# driver2.net
KiCad netlist of a schematic drawn in Altium Designer
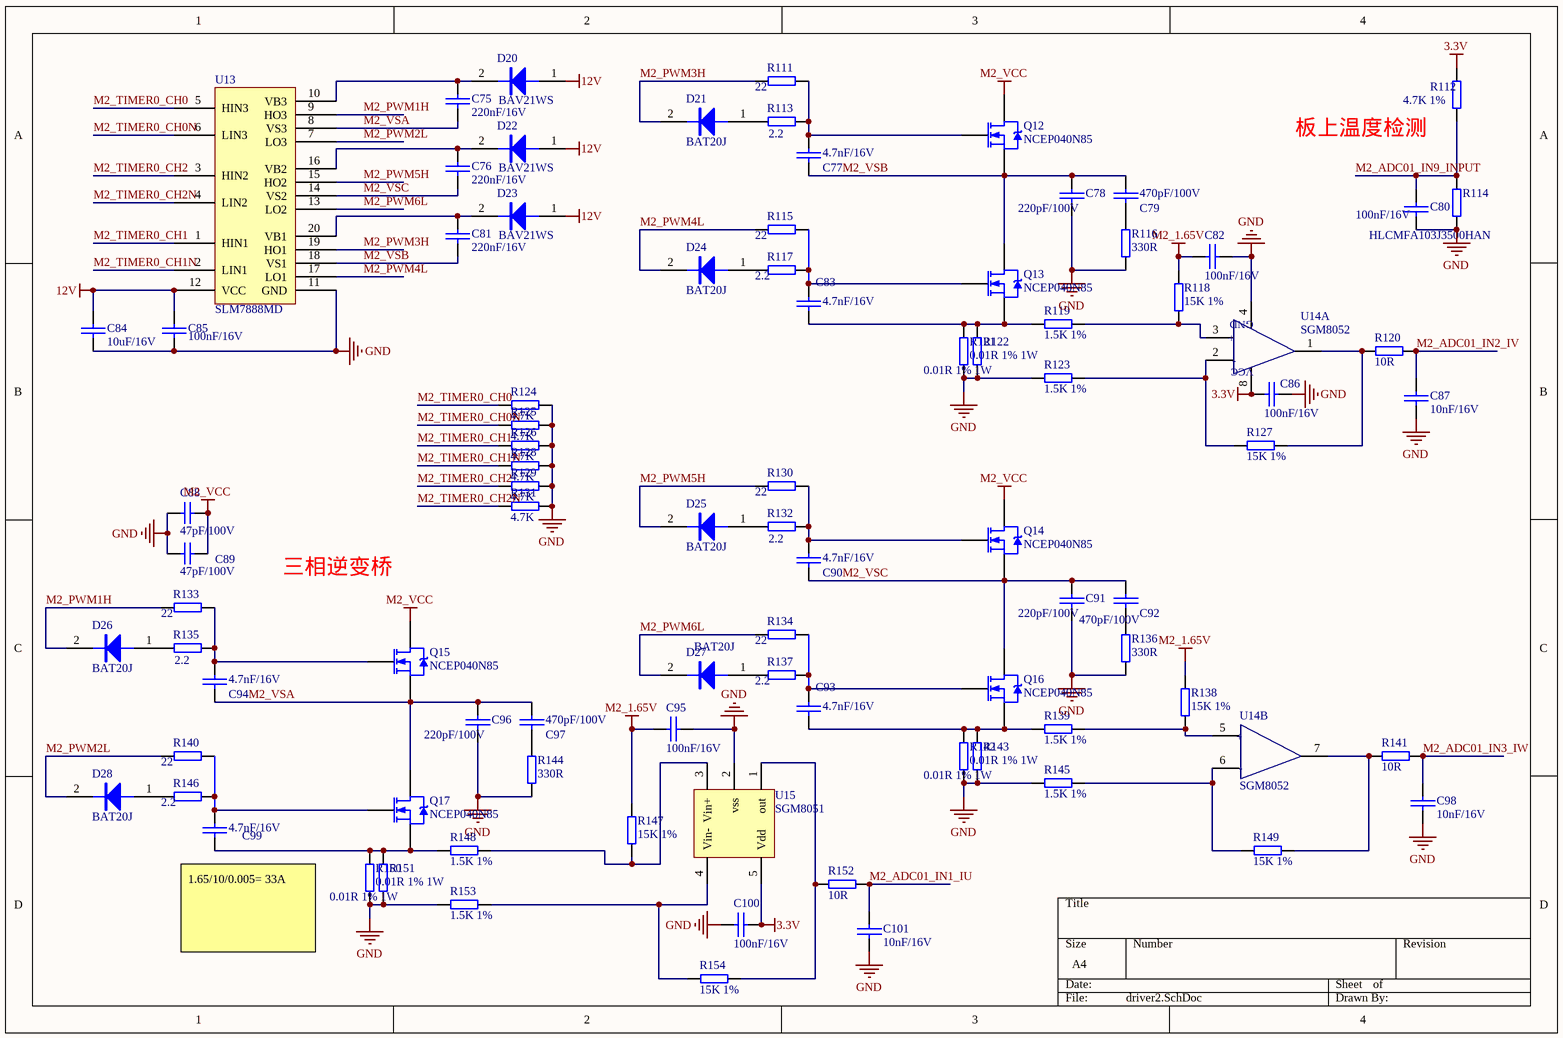
[diagram p0: driver2.SchDoc]

(export (version "E")
  (design (tool "Eeschema 10.0.6"))
  (components
    (comp (ref "C75")
      (value "220nF/16V")
      (footprint "C0402")
      (description "Capacitor")
      (libsource (lib "*") (part "CAP"))
    )
    (comp (ref "C76")
      (value "220nF/16V")
      (footprint "C0402")
      (description "Capacitor")
      (libsource (lib "*") (part "CAP"))
    )
    (comp (ref "C77")
      (value "4.7nF/16V")
      (footprint "C0402")
      (description "Capacitor")
      (libsource (lib "*") (part "CAP"))
    )
    (comp (ref "C78")
      (value "220pF/100V")
      (footprint "C0805")
      (description "Capacitor")
      (libsource (lib "*") (part "CAP"))
    )
    (comp (ref "C79")
      (value "470pF/100V")
      (footprint "C0805")
      (description "Capacitor")
      (libsource (lib "*") (part "CAP"))
    )
    (comp (ref "C80")
      (value "100nF/16V")
      (footprint "C0402")
      (description "Capacitor")
      (libsource (lib "*") (part "CAP"))
    )
    (comp (ref "C81")
      (value "220nF/16V")
      (footprint "C0402")
      (description "Capacitor")
      (libsource (lib "*") (part "CAP"))
    )
    (comp (ref "C82")
      (value "100nF/16V")
      (footprint "C0402")
      (description "Capacitor")
      (libsource (lib "*") (part "CAP"))
    )
    (comp (ref "C83")
      (value "4.7nF/16V")
      (footprint "C0402")
      (description "Capacitor")
      (libsource (lib "*") (part "CAP"))
    )
    (comp (ref "C84")
      (value "10uF/16V")
      (footprint "C0805")
      (description "Capacitor")
      (libsource (lib "*") (part "CAP"))
    )
    (comp (ref "C85")
      (value "100nF/16V")
      (footprint "C0603")
      (description "Capacitor")
      (libsource (lib "*") (part "CAP"))
    )
    (comp (ref "C86")
      (value "100nF/16V")
      (footprint "C0402")
      (description "Capacitor")
      (libsource (lib "*") (part "CAP"))
    )
    (comp (ref "C87")
      (value "10nF/16V")
      (footprint "C0402")
      (description "Capacitor")
      (libsource (lib "*") (part "CAP"))
    )
    (comp (ref "C88") (value "47pF/100V") (footprint "C1206") (libsource (lib "zijianku") (part "cap")))
    (comp (ref "C89") (value "47pF/100V") (footprint "C1206") (libsource (lib "zijianku") (part "cap")))
    (comp (ref "C90")
      (value "4.7nF/16V")
      (footprint "C0402")
      (description "Capacitor")
      (libsource (lib "*") (part "CAP"))
    )
    (comp (ref "C91")
      (value "220pF/100V")
      (footprint "C0805")
      (description "Capacitor")
      (libsource (lib "*") (part "CAP"))
    )
    (comp (ref "C92")
      (value "470pF/100V")
      (footprint "C0805")
      (description "Capacitor")
      (libsource (lib "*") (part "CAP"))
    )
    (comp (ref "C93")
      (value "4.7nF/16V")
      (footprint "C0402")
      (description "Capacitor")
      (libsource (lib "*") (part "CAP"))
    )
    (comp (ref "C94")
      (value "4.7nF/16V")
      (footprint "C0402")
      (description "Capacitor")
      (libsource (lib "*") (part "CAP"))
    )
    (comp (ref "C95")
      (value "100nF/16V")
      (footprint "C0402")
      (description "Capacitor")
      (libsource (lib "*") (part "CAP"))
    )
    (comp (ref "C96")
      (value "220pF/100V")
      (footprint "C0805")
      (description "Capacitor")
      (libsource (lib "*") (part "CAP"))
    )
    (comp (ref "C97")
      (value "470pF/100V")
      (footprint "C0805")
      (description "Capacitor")
      (libsource (lib "*") (part "CAP"))
    )
    (comp (ref "C98")
      (value "10nF/16V")
      (footprint "C0402")
      (description "Capacitor")
      (libsource (lib "*") (part "CAP"))
    )
    (comp (ref "C99")
      (value "4.7nF/16V")
      (footprint "C0402")
      (description "Capacitor")
      (libsource (lib "*") (part "CAP"))
    )
    (comp (ref "C100")
      (value "100nF/16V")
      (footprint "C0402")
      (description "Capacitor")
      (libsource (lib "*") (part "CAP"))
    )
    (comp (ref "C101")
      (value "10nF/16V")
      (footprint "C0402")
      (description "Capacitor")
      (libsource (lib "*") (part "CAP"))
    )
    (comp (ref "D20") (value "BAV21WS") (footprint "SOD-323") (libsource (lib "*") (part "DIODE")))
    (comp (ref "D21") (value "BAT20J") (footprint "SOD-323") (libsource (lib "*") (part "DIODE")))
    (comp (ref "D22") (value "BAV21WS") (footprint "SOD-323") (libsource (lib "*") (part "DIODE")))
    (comp (ref "D23") (value "BAV21WS") (footprint "SOD-323") (libsource (lib "*") (part "DIODE")))
    (comp (ref "D24") (value "BAT20J") (footprint "SOD-323") (libsource (lib "*") (part "DIODE")))
    (comp (ref "D25") (value "BAT20J") (footprint "SOD-323") (libsource (lib "*") (part "DIODE")))
    (comp (ref "D26") (value "BAT20J") (footprint "SOD-323") (libsource (lib "*") (part "DIODE")))
    (comp (ref "D27") (value "BAT20J") (footprint "SOD-323") (libsource (lib "*") (part "DIODE")))
    (comp (ref "D28") (value "BAT20J") (footprint "SOD-323") (libsource (lib "*") (part "DIODE")))
    (comp (ref "Q12")
      (value "NCEP040N85")
      (footprint "TO-220ABN")
      (libsource (lib "zijianku") (part "N-channel Enhancement MOS"))
    )
    (comp (ref "Q13")
      (value "NCEP040N85")
      (footprint "TO-220ABN")
      (libsource (lib "zijianku") (part "N-channel Enhancement MOS"))
    )
    (comp (ref "Q14")
      (value "NCEP040N85")
      (footprint "TO-220ABN")
      (libsource (lib "zijianku") (part "N-channel Enhancement MOS"))
    )
    (comp (ref "Q15")
      (value "NCEP040N85")
      (footprint "TO-220ABN")
      (libsource (lib "zijianku") (part "N-channel Enhancement MOS"))
    )
    (comp (ref "Q16")
      (value "NCEP040N85")
      (footprint "TO-220ABN")
      (libsource (lib "zijianku") (part "N-channel Enhancement MOS"))
    )
    (comp (ref "Q17")
      (value "NCEP040N85")
      (footprint "TO-220ABN")
      (libsource (lib "zijianku") (part "N-channel Enhancement MOS"))
    )
    (comp (ref "R111") (value "22") (footprint "R0603") (libsource (lib "*") (part "R")))
    (comp (ref "R112") (value "4.7K 1%") (footprint "R0402") (libsource (lib "*") (part "R")))
    (comp (ref "R113") (value "2.2") (footprint "R0603") (libsource (lib "*") (part "R")))
    (comp (ref "R114") (value "HLCMFA103J3500HAN") (footprint "R0603") (libsource (lib "*") (part "R")))
    (comp (ref "R115") (value "22") (footprint "R0603") (libsource (lib "*") (part "R")))
    (comp (ref "R116") (value "330R") (footprint "R1206") (libsource (lib "zijianku") (part "Resistance")))
    (comp (ref "R117") (value "2.2") (footprint "R0603") (libsource (lib "*") (part "R")))
    (comp (ref "R118") (value "15K 1%") (footprint "R0402") (libsource (lib "zijianku") (part "Resistance")))
    (comp (ref "R119") (value "1.5K 1%") (footprint "R0402") (libsource (lib "zijianku") (part "Resistance")))
    (comp (ref "R120") (value "10R") (footprint "R0402") (libsource (lib "zijianku") (part "Resistance")))
    (comp (ref "R121")
      (value "0.01R 1% 1W")
      (footprint "R1210")
      (libsource (lib "zijianku") (part "Resistance"))
    )
    (comp (ref "R122")
      (value "0.01R 1% 1W")
      (footprint "R1210")
      (libsource (lib "zijianku") (part "Resistance"))
    )
    (comp (ref "R123") (value "1.5K 1%") (footprint "R0402") (libsource (lib "zijianku") (part "Resistance")))
    (comp (ref "R124") (value "4.7K") (footprint "R0402") (libsource (lib "*") (part "R")))
    (comp (ref "R125") (value "4.7K") (footprint "R0402") (libsource (lib "*") (part "R")))
    (comp (ref "R126") (value "4.7K") (footprint "R0402") (libsource (lib "*") (part "R")))
    (comp (ref "R127") (value "15K 1%") (footprint "R0402") (libsource (lib "zijianku") (part "Resistance")))
    (comp (ref "R128") (value "4.7K") (footprint "R0402") (libsource (lib "*") (part "R")))
    (comp (ref "R129") (value "4.7K") (footprint "R0402") (libsource (lib "*") (part "R")))
    (comp (ref "R130") (value "22") (footprint "R0603") (libsource (lib "*") (part "R")))
    (comp (ref "R131") (value "4.7K") (footprint "R0402") (libsource (lib "*") (part "R")))
    (comp (ref "R132") (value "2.2") (footprint "R0603") (libsource (lib "*") (part "R")))
    (comp (ref "R133") (value "22") (footprint "R0603") (libsource (lib "*") (part "R")))
    (comp (ref "R134") (value "22") (footprint "R0603") (libsource (lib "*") (part "R")))
    (comp (ref "R135") (value "2.2") (footprint "R0603") (libsource (lib "*") (part "R")))
    (comp (ref "R136") (value "330R") (footprint "R1206") (libsource (lib "zijianku") (part "Resistance")))
    (comp (ref "R137") (value "2.2") (footprint "R0603") (libsource (lib "*") (part "R")))
    (comp (ref "R138") (value "15K 1%") (footprint "R0402") (libsource (lib "zijianku") (part "Resistance")))
    (comp (ref "R139") (value "1.5K 1%") (footprint "R0402") (libsource (lib "zijianku") (part "Resistance")))
    (comp (ref "R140") (value "22") (footprint "R0603") (libsource (lib "*") (part "R")))
    (comp (ref "R141") (value "10R") (footprint "R0402") (libsource (lib "zijianku") (part "Resistance")))
    (comp (ref "R142")
      (value "0.01R 1% 1W")
      (footprint "R1210")
      (libsource (lib "zijianku") (part "Resistance"))
    )
    (comp (ref "R143")
      (value "0.01R 1% 1W")
      (footprint "R1210")
      (libsource (lib "zijianku") (part "Resistance"))
    )
    (comp (ref "R144") (value "330R") (footprint "R1206") (libsource (lib "zijianku") (part "Resistance")))
    (comp (ref "R145") (value "1.5K 1%") (footprint "R0402") (libsource (lib "zijianku") (part "Resistance")))
    (comp (ref "R146") (value "2.2") (footprint "R0603") (libsource (lib "*") (part "R")))
    (comp (ref "R147") (value "15K 1%") (footprint "R0402") (libsource (lib "zijianku") (part "Resistance")))
    (comp (ref "R148") (value "1.5K 1%") (footprint "R0402") (libsource (lib "zijianku") (part "Resistance")))
    (comp (ref "R149") (value "15K 1%") (footprint "R0402") (libsource (lib "zijianku") (part "Resistance")))
    (comp (ref "R150")
      (value "0.01R 1% 1W")
      (footprint "R1210")
      (libsource (lib "zijianku") (part "Resistance"))
    )
    (comp (ref "R151")
      (value "0.01R 1% 1W")
      (footprint "R1210")
      (libsource (lib "zijianku") (part "Resistance"))
    )
    (comp (ref "R152") (value "10R") (footprint "R0402") (libsource (lib "zijianku") (part "Resistance")))
    (comp (ref "R153") (value "1.5K 1%") (footprint "R0402") (libsource (lib "zijianku") (part "Resistance")))
    (comp (ref "R154") (value "15K 1%") (footprint "R0402") (libsource (lib "zijianku") (part "Resistance")))
    (comp (ref "U13")
      (value "SLM7888MD")
      (footprint "TSSOP-20")
      (description "SILLUMIN")
      (libsource (lib "zijianku") (part "SLM7888"))
    )
    (comp (ref "U14")
      (value "SGM8052")
      (footprint "VSSOP/MSOP-8")
      (description "圣邦微电子")
      (libsource (lib "Common Device") (part "LM393"))
    )
    (comp (ref "U15")
      (value "SGM8051")
      (footprint "SOT-23(5)")
      (description "圣邦微电子")
      (libsource (lib "Common Device") (part "LMV7239"))
    )
  )
  (nets
    (net (code "1") (name "/M2_ADC01_IN1_IU") (class "Default")
      (node (ref "C101") (pin "1") (pinfunction "1_1") (pintype "passive"))
      (node (ref "R152") (pin "1") (pintype "passive"))
    )
    (net (code "2") (name "/M2_ADC01_IN2_IV") (class "Default")
      (node (ref "C87") (pin "1") (pinfunction "1_1") (pintype "passive"))
      (node (ref "R120") (pin "1") (pintype "passive"))
    )
    (net (code "3") (name "/M2_ADC01_IN3_IW") (class "Default")
      (node (ref "C98") (pin "1") (pinfunction "1_1") (pintype "passive"))
      (node (ref "R141") (pin "1") (pintype "passive"))
    )
    (net (code "4") (name "/M2_ADC01_IN9_INPUT") (class "Default")
      (node (ref "C80") (pin "1") (pinfunction "1_1") (pintype "passive"))
      (node (ref "R112") (pin "1") (pinfunction "1_1") (pintype "passive"))
      (node (ref "R114") (pin "2") (pinfunction "2_2") (pintype "passive"))
    )
    (net (code "5") (name "/M2_PWM1H") (class "Default")
      (node (ref "D26") (pin "2") (pinfunction "K_2") (pintype "passive"))
      (node (ref "R133") (pin "2") (pinfunction "2_2") (pintype "passive"))
      (node (ref "U13") (pin "9") (pinfunction "HO3_9") (pintype "passive"))
    )
    (net (code "6") (name "/M2_PWM2L") (class "Default")
      (node (ref "D28") (pin "2") (pinfunction "K_2") (pintype "passive"))
      (node (ref "R140") (pin "2") (pinfunction "2_2") (pintype "passive"))
      (node (ref "U13") (pin "7") (pinfunction "LO3_7") (pintype "passive"))
    )
    (net (code "7") (name "/M2_PWM3H") (class "Default")
      (node (ref "D21") (pin "2") (pinfunction "K_2") (pintype "passive"))
      (node (ref "R111") (pin "2") (pinfunction "2_2") (pintype "passive"))
      (node (ref "U13") (pin "19") (pinfunction "HO1_19") (pintype "passive"))
    )
    (net (code "8") (name "/M2_PWM4L") (class "Default")
      (node (ref "D24") (pin "2") (pinfunction "K_2") (pintype "passive"))
      (node (ref "R115") (pin "2") (pinfunction "2_2") (pintype "passive"))
      (node (ref "U13") (pin "17") (pinfunction "LO1_17") (pintype "passive"))
    )
    (net (code "9") (name "/M2_PWM5H") (class "Default")
      (node (ref "D25") (pin "2") (pinfunction "K_2") (pintype "passive"))
      (node (ref "R130") (pin "2") (pinfunction "2_2") (pintype "passive"))
      (node (ref "U13") (pin "15") (pinfunction "HO2_15") (pintype "passive"))
    )
    (net (code "10") (name "/M2_PWM6L") (class "Default")
      (node (ref "D27") (pin "2") (pinfunction "K_2") (pintype "passive"))
      (node (ref "R134") (pin "2") (pinfunction "2_2") (pintype "passive"))
      (node (ref "U13") (pin "13") (pinfunction "LO2_13") (pintype "passive"))
    )
    (net (code "11") (name "/M2_TIMER0_CH0") (class "Default")
      (node (ref "R124") (pin "1") (pinfunction "1_1") (pintype "passive"))
      (node (ref "U13") (pin "5") (pinfunction "HIN3_5") (pintype "passive"))
    )
    (net (code "12") (name "/M2_TIMER0_CH0N") (class "Default")
      (node (ref "R125") (pin "1") (pinfunction "1_1") (pintype "passive"))
      (node (ref "U13") (pin "6") (pinfunction "LIN3_6") (pintype "passive"))
    )
    (net (code "13") (name "/M2_TIMER0_CH1") (class "Default")
      (node (ref "R126") (pin "1") (pinfunction "1_1") (pintype "passive"))
      (node (ref "U13") (pin "1") (pinfunction "HIN1_1") (pintype "passive"))
    )
    (net (code "14") (name "/M2_TIMER0_CH1N") (class "Default")
      (node (ref "R128") (pin "1") (pinfunction "1_1") (pintype "passive"))
      (node (ref "U13") (pin "2") (pinfunction "LIN1_2") (pintype "passive"))
    )
    (net (code "15") (name "/M2_TIMER0_CH2") (class "Default")
      (node (ref "R129") (pin "1") (pinfunction "1_1") (pintype "passive"))
      (node (ref "U13") (pin "3") (pinfunction "HIN2_3") (pintype "passive"))
    )
    (net (code "16") (name "/M2_TIMER0_CH2N") (class "Default")
      (node (ref "R131") (pin "1") (pinfunction "1_1") (pintype "passive"))
      (node (ref "U13") (pin "4") (pinfunction "LIN2_4") (pintype "passive"))
    )
    (net (code "17") (name "/M2_VSA") (class "Default")
      (node (ref "C75") (pin "1") (pinfunction "1_1") (pintype "passive"))
      (node (ref "C94") (pin "2") (pinfunction "2_2") (pintype "passive"))
      (node (ref "C96") (pin "2") (pinfunction "2_2") (pintype "passive"))
      (node (ref "C97") (pin "1") (pinfunction "1_1") (pintype "passive"))
      (node (ref "Q15") (pin "2") (pinfunction "S_2") (pintype "passive"))
      (node (ref "Q17") (pin "3") (pinfunction "D_3") (pintype "passive"))
      (node (ref "U13") (pin "8") (pinfunction "VS3_8") (pintype "passive"))
    )
    (net (code "18") (name "/M2_VSB") (class "Default")
      (node (ref "C77") (pin "2") (pinfunction "2_2") (pintype "passive"))
      (node (ref "C78") (pin "2") (pinfunction "2_2") (pintype "passive"))
      (node (ref "C79") (pin "1") (pinfunction "1_1") (pintype "passive"))
      (node (ref "C81") (pin "1") (pinfunction "1_1") (pintype "passive"))
      (node (ref "Q12") (pin "2") (pinfunction "S_2") (pintype "passive"))
      (node (ref "Q13") (pin "3") (pinfunction "D_3") (pintype "passive"))
      (node (ref "U13") (pin "18") (pinfunction "VS1_18") (pintype "passive"))
    )
    (net (code "19") (name "/M2_VSC") (class "Default")
      (node (ref "C76") (pin "1") (pinfunction "1_1") (pintype "passive"))
      (node (ref "C90") (pin "2") (pinfunction "2_2") (pintype "passive"))
      (node (ref "C91") (pin "2") (pinfunction "2_2") (pintype "passive"))
      (node (ref "C92") (pin "1") (pinfunction "1_1") (pintype "passive"))
      (node (ref "Q14") (pin "2") (pinfunction "S_2") (pintype "passive"))
      (node (ref "Q16") (pin "3") (pinfunction "D_3") (pintype "passive"))
      (node (ref "U13") (pin "14") (pinfunction "VS2_14") (pintype "passive"))
    )
    (net (code "20") (name "3.3V") (class "Default")
      (node (ref "C100") (pin "2") (pinfunction "2_2") (pintype "passive"))
      (node (ref "C86") (pin "2") (pinfunction "2_2") (pintype "passive"))
      (node (ref "R112") (pin "2") (pinfunction "2_2") (pintype "passive"))
      (node (ref "U14") (pin "8") (pinfunction "VCC_8") (pintype "passive"))
      (node (ref "U15") (pin "5") (pinfunction "Vdd_5") (pintype "passive"))
    )
    (net (code "21") (name "12V") (class "Default")
      (node (ref "C84") (pin "2") (pinfunction "2_2") (pintype "passive"))
      (node (ref "C85") (pin "2") (pinfunction "2_2") (pintype "passive"))
      (node (ref "D20") (pin "1") (pinfunction "A_1") (pintype "passive"))
      (node (ref "D22") (pin "1") (pinfunction "A_1") (pintype "passive"))
      (node (ref "D23") (pin "1") (pinfunction "A_1") (pintype "passive"))
      (node (ref "U13") (pin "12") (pinfunction "VCC_12") (pintype "passive"))
    )
    (net (code "22") (name "GND") (class "Default")
      (node (ref "C100") (pin "1") (pinfunction "1_1") (pintype "passive"))
      (node (ref "C101") (pin "2") (pinfunction "2_2") (pintype "passive"))
      (node (ref "C78") (pin "1") (pinfunction "1_1") (pintype "passive"))
      (node (ref "C80") (pin "2") (pinfunction "2_2") (pintype "passive"))
      (node (ref "C82") (pin "1") (pinfunction "1_1") (pintype "passive"))
      (node (ref "C84") (pin "1") (pinfunction "1_1") (pintype "passive"))
      (node (ref "C85") (pin "1") (pinfunction "1_1") (pintype "passive"))
      (node (ref "C86") (pin "1") (pinfunction "1_1") (pintype "passive"))
      (node (ref "C87") (pin "2") (pinfunction "2_2") (pintype "passive"))
      (node (ref "C88") (pin "2") (pinfunction "1_2") (pintype "passive"))
      (node (ref "C89") (pin "2") (pinfunction "1_2") (pintype "passive"))
      (node (ref "C91") (pin "1") (pinfunction "1_1") (pintype "passive"))
      (node (ref "C95") (pin "1") (pinfunction "1_1") (pintype "passive"))
      (node (ref "C96") (pin "1") (pinfunction "1_1") (pintype "passive"))
      (node (ref "C98") (pin "2") (pinfunction "2_2") (pintype "passive"))
      (node (ref "R114") (pin "1") (pinfunction "1_1") (pintype "passive"))
      (node (ref "R116") (pin "1") (pintype "passive"))
      (node (ref "R121") (pin "2") (pintype "passive"))
      (node (ref "R122") (pin "2") (pintype "passive"))
      (node (ref "R123") (pin "2") (pintype "passive"))
      (node (ref "R124") (pin "2") (pinfunction "2_2") (pintype "passive"))
      (node (ref "R125") (pin "2") (pinfunction "2_2") (pintype "passive"))
      (node (ref "R126") (pin "2") (pinfunction "2_2") (pintype "passive"))
      (node (ref "R128") (pin "2") (pinfunction "2_2") (pintype "passive"))
      (node (ref "R129") (pin "2") (pinfunction "2_2") (pintype "passive"))
      (node (ref "R131") (pin "2") (pinfunction "2_2") (pintype "passive"))
      (node (ref "R136") (pin "1") (pintype "passive"))
      (node (ref "R142") (pin "2") (pintype "passive"))
      (node (ref "R143") (pin "2") (pintype "passive"))
      (node (ref "R144") (pin "1") (pintype "passive"))
      (node (ref "R145") (pin "2") (pintype "passive"))
      (node (ref "R150") (pin "2") (pintype "passive"))
      (node (ref "R151") (pin "2") (pintype "passive"))
      (node (ref "R153") (pin "2") (pintype "passive"))
      (node (ref "U13") (pin "11") (pinfunction "GND_11") (pintype "passive"))
      (node (ref "U14") (pin "4") (pinfunction "GND_4") (pintype "passive"))
      (node (ref "U15") (pin "2") (pinfunction "vss_2") (pintype "passive"))
    )
    (net (code "23") (name "M2_1.65V") (class "Default")
      (node (ref "C82") (pin "2") (pinfunction "2_2") (pintype "passive"))
      (node (ref "C95") (pin "2") (pinfunction "2_2") (pintype "passive"))
      (node (ref "R118") (pin "1") (pintype "passive"))
      (node (ref "R138") (pin "1") (pintype "passive"))
      (node (ref "R147") (pin "1") (pintype "passive"))
    )
    (net (code "24") (name "M2_VCC") (class "Default")
      (node (ref "C88") (pin "1") (pinfunction "0_1") (pintype "passive"))
      (node (ref "C89") (pin "1") (pinfunction "0_1") (pintype "passive"))
      (node (ref "Q12") (pin "3") (pinfunction "D_3") (pintype "passive"))
      (node (ref "Q14") (pin "3") (pinfunction "D_3") (pintype "passive"))
      (node (ref "Q15") (pin "3") (pinfunction "D_3") (pintype "passive"))
    )
    (net (code "25") (name "Net-(C79-Pad2)") (class "Default")
      (node (ref "C79") (pin "2") (pinfunction "2_2") (pintype "passive"))
      (node (ref "R116") (pin "2") (pintype "passive"))
    )
    (net (code "26") (name "Net-(C92-Pad2)") (class "Default")
      (node (ref "C92") (pin "2") (pinfunction "2_2") (pintype "passive"))
      (node (ref "R136") (pin "2") (pintype "passive"))
    )
    (net (code "27") (name "Net-(C97-Pad2)") (class "Default")
      (node (ref "C97") (pin "2") (pinfunction "2_2") (pintype "passive"))
      (node (ref "R144") (pin "2") (pintype "passive"))
    )
    (net (code "28") (name "Net-(D20-K)") (class "Default")
      (node (ref "C75") (pin "2") (pinfunction "2_2") (pintype "passive"))
      (node (ref "D20") (pin "2") (pinfunction "K_2") (pintype "passive"))
      (node (ref "U13") (pin "10") (pinfunction "VB3_10") (pintype "passive"))
    )
    (net (code "29") (name "Net-(D21-A)") (class "Default")
      (node (ref "D21") (pin "1") (pinfunction "A_1") (pintype "passive"))
      (node (ref "R113") (pin "1") (pinfunction "1_1") (pintype "passive"))
    )
    (net (code "30") (name "Net-(D22-K)") (class "Default")
      (node (ref "C76") (pin "2") (pinfunction "2_2") (pintype "passive"))
      (node (ref "D22") (pin "2") (pinfunction "K_2") (pintype "passive"))
      (node (ref "U13") (pin "16") (pinfunction "VB2_16") (pintype "passive"))
    )
    (net (code "31") (name "Net-(D23-K)") (class "Default")
      (node (ref "C81") (pin "2") (pinfunction "2_2") (pintype "passive"))
      (node (ref "D23") (pin "2") (pinfunction "K_2") (pintype "passive"))
      (node (ref "U13") (pin "20") (pinfunction "VB1_20") (pintype "passive"))
    )
    (net (code "32") (name "Net-(D24-A)") (class "Default")
      (node (ref "D24") (pin "1") (pinfunction "A_1") (pintype "passive"))
      (node (ref "R117") (pin "1") (pinfunction "1_1") (pintype "passive"))
    )
    (net (code "33") (name "Net-(D25-A)") (class "Default")
      (node (ref "D25") (pin "1") (pinfunction "A_1") (pintype "passive"))
      (node (ref "R132") (pin "1") (pinfunction "1_1") (pintype "passive"))
    )
    (net (code "34") (name "Net-(D26-A)") (class "Default")
      (node (ref "D26") (pin "1") (pinfunction "A_1") (pintype "passive"))
      (node (ref "R135") (pin "1") (pinfunction "1_1") (pintype "passive"))
    )
    (net (code "35") (name "Net-(D27-A)") (class "Default")
      (node (ref "D27") (pin "1") (pinfunction "A_1") (pintype "passive"))
      (node (ref "R137") (pin "1") (pinfunction "1_1") (pintype "passive"))
    )
    (net (code "36") (name "Net-(D28-A)") (class "Default")
      (node (ref "D28") (pin "1") (pinfunction "A_1") (pintype "passive"))
      (node (ref "R146") (pin "1") (pinfunction "1_1") (pintype "passive"))
    )
    (net (code "37") (name "Net-(Q12-G)") (class "Default")
      (node (ref "C77") (pin "1") (pinfunction "1_1") (pintype "passive"))
      (node (ref "Q12") (pin "1") (pinfunction "G_1") (pintype "passive"))
      (node (ref "R111") (pin "1") (pinfunction "1_1") (pintype "passive"))
      (node (ref "R113") (pin "2") (pinfunction "2_2") (pintype "passive"))
    )
    (net (code "38") (name "Net-(Q13-G)") (class "Default")
      (node (ref "C83") (pin "1") (pinfunction "1_1") (pintype "passive"))
      (node (ref "Q13") (pin "1") (pinfunction "G_1") (pintype "passive"))
      (node (ref "R115") (pin "1") (pinfunction "1_1") (pintype "passive"))
      (node (ref "R117") (pin "2") (pinfunction "2_2") (pintype "passive"))
    )
    (net (code "39") (name "Net-(Q13-S)") (class "Default")
      (node (ref "C83") (pin "2") (pinfunction "2_2") (pintype "passive"))
      (node (ref "Q13") (pin "2") (pinfunction "S_2") (pintype "passive"))
      (node (ref "R119") (pin "2") (pintype "passive"))
      (node (ref "R121") (pin "1") (pintype "passive"))
      (node (ref "R122") (pin "1") (pintype "passive"))
    )
    (net (code "40") (name "Net-(Q14-G)") (class "Default")
      (node (ref "C90") (pin "1") (pinfunction "1_1") (pintype "passive"))
      (node (ref "Q14") (pin "1") (pinfunction "G_1") (pintype "passive"))
      (node (ref "R130") (pin "1") (pinfunction "1_1") (pintype "passive"))
      (node (ref "R132") (pin "2") (pinfunction "2_2") (pintype "passive"))
    )
    (net (code "41") (name "Net-(Q15-G)") (class "Default")
      (node (ref "C94") (pin "1") (pinfunction "1_1") (pintype "passive"))
      (node (ref "Q15") (pin "1") (pinfunction "G_1") (pintype "passive"))
      (node (ref "R133") (pin "1") (pinfunction "1_1") (pintype "passive"))
      (node (ref "R135") (pin "2") (pinfunction "2_2") (pintype "passive"))
    )
    (net (code "42") (name "Net-(Q16-G)") (class "Default")
      (node (ref "C93") (pin "1") (pinfunction "1_1") (pintype "passive"))
      (node (ref "Q16") (pin "1") (pinfunction "G_1") (pintype "passive"))
      (node (ref "R134") (pin "1") (pinfunction "1_1") (pintype "passive"))
      (node (ref "R137") (pin "2") (pinfunction "2_2") (pintype "passive"))
    )
    (net (code "43") (name "Net-(Q16-S)") (class "Default")
      (node (ref "C93") (pin "2") (pinfunction "2_2") (pintype "passive"))
      (node (ref "Q16") (pin "2") (pinfunction "S_2") (pintype "passive"))
      (node (ref "R139") (pin "2") (pintype "passive"))
      (node (ref "R142") (pin "1") (pintype "passive"))
      (node (ref "R143") (pin "1") (pintype "passive"))
    )
    (net (code "44") (name "Net-(Q17-G)") (class "Default")
      (node (ref "C99") (pin "1") (pinfunction "1_1") (pintype "passive"))
      (node (ref "Q17") (pin "1") (pinfunction "G_1") (pintype "passive"))
      (node (ref "R140") (pin "1") (pinfunction "1_1") (pintype "passive"))
      (node (ref "R146") (pin "2") (pinfunction "2_2") (pintype "passive"))
    )
    (net (code "45") (name "Net-(Q17-S)") (class "Default")
      (node (ref "C99") (pin "2") (pinfunction "2_2") (pintype "passive"))
      (node (ref "Q17") (pin "2") (pinfunction "S_2") (pintype "passive"))
      (node (ref "R148") (pin "2") (pintype "passive"))
      (node (ref "R150") (pin "1") (pintype "passive"))
      (node (ref "R151") (pin "1") (pintype "passive"))
    )
    (net (code "46") (name "Net-(R118-Pad2)") (class "Default")
      (node (ref "R118") (pin "2") (pintype "passive"))
      (node (ref "R119") (pin "1") (pintype "passive"))
      (node (ref "U14") (pin "3") (pinfunction "-_3") (pintype "passive"))
    )
    (net (code "47") (name "Net-(R123-Pad1)") (class "Default")
      (node (ref "R123") (pin "1") (pintype "passive"))
      (node (ref "R127") (pin "2") (pintype "passive"))
      (node (ref "U14") (pin "2") (pinfunction "-_2") (pintype "passive"))
    )
    (net (code "48") (name "Net-(U14A-OUT1)") (class "Default")
      (node (ref "R120") (pin "2") (pintype "passive"))
      (node (ref "R127") (pin "1") (pintype "passive"))
      (node (ref "U14") (pin "1") (pinfunction "OUT1_1") (pintype "passive"))
    )
    (net (code "49") (name "Net-(U14B-+)") (class "Default")
      (node (ref "R138") (pin "2") (pintype "passive"))
      (node (ref "R139") (pin "1") (pintype "passive"))
      (node (ref "U14") (pin "5") (pinfunction "+_5") (pintype "passive"))
    )
    (net (code "50") (name "Net-(U14B--)") (class "Default")
      (node (ref "R145") (pin "1") (pintype "passive"))
      (node (ref "R149") (pin "2") (pintype "passive"))
      (node (ref "U14") (pin "6") (pinfunction "-_6") (pintype "passive"))
    )
    (net (code "51") (name "Net-(U14B-OUT2)") (class "Default")
      (node (ref "R141") (pin "2") (pintype "passive"))
      (node (ref "R149") (pin "1") (pintype "passive"))
      (node (ref "U14") (pin "7") (pinfunction "OUT2_7") (pintype "passive"))
    )
    (net (code "52") (name "Net-(U15-Vin+)") (class "Default")
      (node (ref "R147") (pin "2") (pintype "passive"))
      (node (ref "R148") (pin "1") (pintype "passive"))
      (node (ref "U15") (pin "3") (pinfunction "Vin+_3") (pintype "passive"))
    )
    (net (code "53") (name "Net-(U15-Vin-)") (class "Default")
      (node (ref "R153") (pin "1") (pintype "passive"))
      (node (ref "R154") (pin "2") (pintype "passive"))
      (node (ref "U15") (pin "4") (pinfunction "Vin-_4") (pintype "passive"))
    )
    (net (code "54") (name "Net-(U15-out)") (class "Default")
      (node (ref "R152") (pin "2") (pintype "passive"))
      (node (ref "R154") (pin "1") (pintype "passive"))
      (node (ref "U15") (pin "1") (pinfunction "out_1") (pintype "passive"))
    )
  )
)
